# attiny84.net
KiCad netlist of a schematic drawn in EAGLE
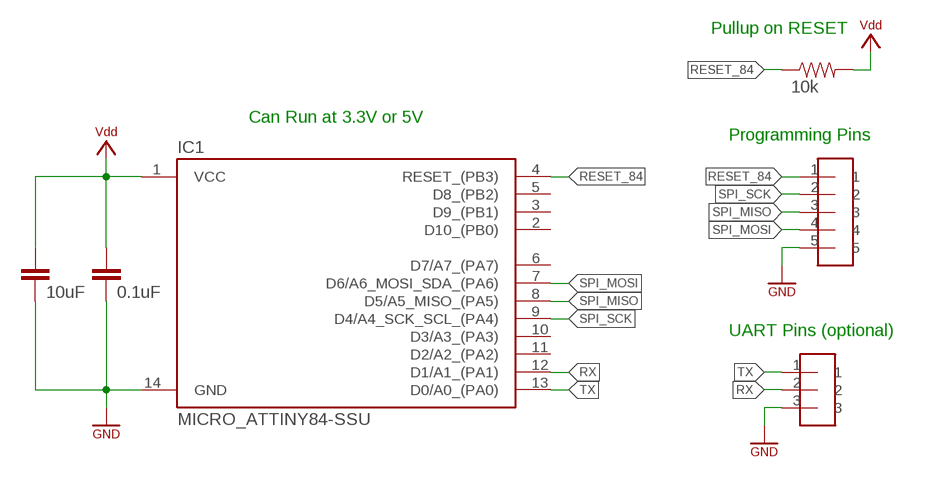
[diagram p0: schematic, sheet 1]

(export (version "E")
  (design (tool "Eeschema 10.0.6"))
  (components
    (comp (ref "C1")
      (value "0.1uF")
      (footprint "eagle-import:0805")
      (libsource (lib "eagle-import") (part "COMPONENT_CAP-0805"))
    )
    (comp (ref "C2")
      (value "10uF")
      (footprint "eagle-import:0805")
      (libsource (lib "eagle-import") (part "COMPONENT_CAP-0805"))
    )
    (comp (ref "IC1")
      (value "MICRO_ATTINY84-SSU")
      (footprint "eagle-import:SOIC14")
      (libsource (lib "eagle-import") (part "MICRO_ATTINY84-SSU"))
    )
    (comp (ref "R1")
      (value "10k")
      (footprint "eagle-import:0805")
      (libsource (lib "eagle-import") (part "COMPONENT_RESISTOR-0805"))
    )
    (comp (ref "U$1")
      (value "HEADER-3-TESTPOINT")
      (footprint "eagle-import:TESTPOINT-3")
      (libsource (lib "eagle-import") (part "HEADER-3-TESTPOINT"))
    )
    (comp (ref "U$2")
      (value "HEADER-5-TESTPOINT")
      (footprint "eagle-import:TESTPOINT-5")
      (libsource (lib "eagle-import") (part "HEADER-5-TESTPOINT"))
    )
  )
  (nets
    (net (code "1") (name "RESET_84") (class "Default")
      (node (ref "IC1") (pin "4") (pinfunction "RESET_(PB3)_4") (pintype "bidirectional"))
      (node (ref "R1") (pin "1") (pinfunction "1_1") (pintype "passive"))
      (node (ref "U$2") (pin "1") (pinfunction "1_1") (pintype "bidirectional"))
    )
    (net (code "2") (name "RX") (class "Default")
      (node (ref "IC1") (pin "12") (pinfunction "D1/A1_(PA1)_12") (pintype "bidirectional"))
      (node (ref "U$1") (pin "2") (pinfunction "2_2") (pintype "bidirectional"))
    )
    (net (code "3") (name "SPI_MISO") (class "Default")
      (node (ref "IC1") (pin "8") (pinfunction "D5/A5_MISO_(PA5)_8") (pintype "bidirectional"))
      (node (ref "U$2") (pin "3") (pinfunction "3_3") (pintype "bidirectional"))
    )
    (net (code "4") (name "SPI_MOSI") (class "Default")
      (node (ref "IC1") (pin "7") (pinfunction "D6/A6_MOSI_SDA_(PA6)_7") (pintype "bidirectional"))
      (node (ref "U$2") (pin "4") (pinfunction "4_4") (pintype "bidirectional"))
    )
    (net (code "5") (name "SPI_SCK") (class "Default")
      (node (ref "IC1") (pin "9") (pinfunction "D4/A4_SCK_SCL_(PA4)_9") (pintype "bidirectional"))
      (node (ref "U$2") (pin "2") (pinfunction "2_2") (pintype "bidirectional"))
    )
    (net (code "6") (name "SYMBOL_GND") (class "Default")
      (node (ref "C1") (pin "2") (pinfunction "2_2") (pintype "passive"))
      (node (ref "C2") (pin "2") (pinfunction "2_2") (pintype "passive"))
      (node (ref "IC1") (pin "14") (pinfunction "GND_14") (pintype "power_in"))
      (node (ref "U$1") (pin "3") (pinfunction "3_3") (pintype "bidirectional"))
      (node (ref "U$2") (pin "5") (pinfunction "5_5") (pintype "bidirectional"))
    )
    (net (code "7") (name "SYMBOL_VDD") (class "Default")
      (node (ref "C1") (pin "1") (pinfunction "1_1") (pintype "passive"))
      (node (ref "C2") (pin "1") (pinfunction "1_1") (pintype "passive"))
      (node (ref "IC1") (pin "1") (pinfunction "VCC_1") (pintype "power_in"))
      (node (ref "R1") (pin "2") (pinfunction "2_2") (pintype "passive"))
    )
    (net (code "8") (name "TX") (class "Default")
      (node (ref "IC1") (pin "13") (pinfunction "D0/A0_(PA0)_13") (pintype "bidirectional"))
      (node (ref "U$1") (pin "1") (pinfunction "1_1") (pintype "bidirectional"))
    )
    (net (code "9") (name "unconnected-(IC1-D2{slash}A2_(PA2)-Pad11)") (class "Default")
      (node (ref "IC1") (pin "11") (pinfunction "D2/A2_(PA2)_11") (pintype "bidirectional"))
    )
    (net (code "10") (name "unconnected-(IC1-D3{slash}A3_(PA3)-Pad10)") (class "Default")
      (node (ref "IC1") (pin "10") (pinfunction "D3/A3_(PA3)_10") (pintype "bidirectional"))
    )
    (net (code "11") (name "unconnected-(IC1-D7{slash}A7_(PA7)-Pad6)") (class "Default")
      (node (ref "IC1") (pin "6") (pinfunction "D7/A7_(PA7)_6") (pintype "bidirectional"))
    )
    (net (code "12") (name "unconnected-(IC1-D8_(PB2)-Pad5)") (class "Default")
      (node (ref "IC1") (pin "5") (pinfunction "D8_(PB2)_5") (pintype "bidirectional"))
    )
    (net (code "13") (name "unconnected-(IC1-D9_(PB1)-Pad3)") (class "Default")
      (node (ref "IC1") (pin "3") (pinfunction "D9_(PB1)_3") (pintype "bidirectional"))
    )
    (net (code "14") (name "unconnected-(IC1-D10_(PB0)-Pad2)") (class "Default")
      (node (ref "IC1") (pin "2") (pinfunction "D10_(PB0)_2") (pintype "bidirectional"))
    )
  )
)
